# Top_Level.net
KiCad netlist of a schematic drawn in Altium Designer
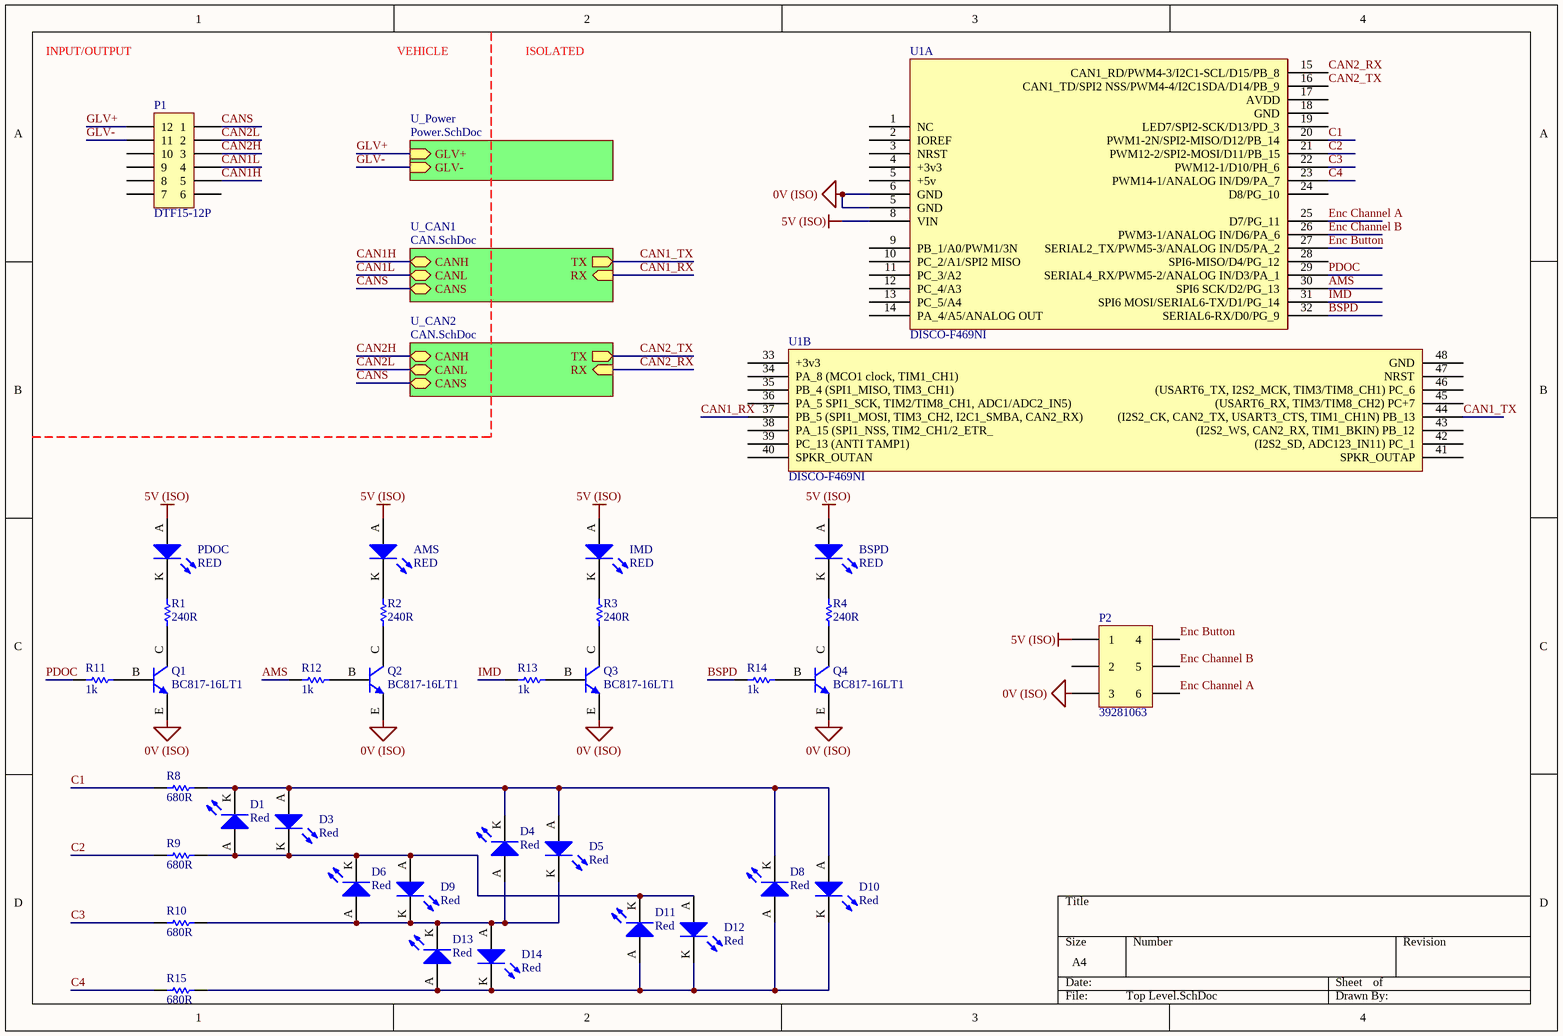
[diagram p0: Top Level.SchDoc]

(export (version "E")
  (design (tool "Eeschema 10.0.6"))
  (components
    (comp (ref "AMS")
      (value "RED")
      (footprint "5MM LED")
      (description "LED RED CLEAR 5MM ROUND T/H")
      (fields (field (name "PART NUMBER") "C503B-GAN-CB0F0791") (field (name "MANUFACTURER") "Cree Inc."))
      (libsource (lib "ts_19-standard-library") (part "LED"))
    )
    (comp (ref "BSPD")
      (value "RED")
      (footprint "5MM LED")
      (description "LED RED CLEAR 5MM ROUND T/H")
      (fields (field (name "PART NUMBER") "C503B-GAN-CB0F0791") (field (name "MANUFACTURER") "Cree Inc."))
      (libsource (lib "ts_19-standard-library") (part "LED"))
    )
    (comp (ref "D1")
      (value "Red")
      (footprint "0805 LED")
      (description "Red LED Indication - Discrete 1.75V 0805 (2012 Metric)")
      (fields (field (name "MANUFACTURER") "ROHM Semiconductor") (field (name "PART NUMBER") "SML-210LTT86"))
      (libsource (lib "ts_19-standard-library") (part "LED"))
    )
    (comp (ref "D3")
      (value "Red")
      (footprint "0805 LED")
      (description "Red LED Indication - Discrete 1.75V 0805 (2012 Metric)")
      (fields (field (name "MANUFACTURER") "ROHM Semiconductor") (field (name "PART NUMBER") "SML-210LTT86"))
      (libsource (lib "ts_19-standard-library") (part "LED"))
    )
    (comp (ref "D4")
      (value "Red")
      (footprint "0805 LED")
      (description "Red LED Indication - Discrete 1.75V 0805 (2012 Metric)")
      (fields (field (name "MANUFACTURER") "ROHM Semiconductor") (field (name "PART NUMBER") "SML-210LTT86"))
      (libsource (lib "ts_19-standard-library") (part "LED"))
    )
    (comp (ref "D5")
      (value "Red")
      (footprint "0805 LED")
      (description "Red LED Indication - Discrete 1.75V 0805 (2012 Metric)")
      (fields (field (name "MANUFACTURER") "ROHM Semiconductor") (field (name "PART NUMBER") "SML-210LTT86"))
      (libsource (lib "ts_19-standard-library") (part "LED"))
    )
    (comp (ref "D6")
      (value "Red")
      (footprint "0805 LED")
      (description "Red LED Indication - Discrete 1.75V 0805 (2012 Metric)")
      (fields (field (name "MANUFACTURER") "ROHM Semiconductor") (field (name "PART NUMBER") "SML-210LTT86"))
      (libsource (lib "ts_19-standard-library") (part "LED"))
    )
    (comp (ref "D8")
      (value "Red")
      (footprint "0805 LED")
      (description "Red LED Indication - Discrete 1.75V 0805 (2012 Metric)")
      (fields (field (name "MANUFACTURER") "ROHM Semiconductor") (field (name "PART NUMBER") "SML-210LTT86"))
      (libsource (lib "ts_19-standard-library") (part "LED"))
    )
    (comp (ref "D9")
      (value "Red")
      (footprint "0805 LED")
      (description "Red LED Indication - Discrete 1.75V 0805 (2012 Metric)")
      (fields (field (name "MANUFACTURER") "ROHM Semiconductor") (field (name "PART NUMBER") "SML-210LTT86"))
      (libsource (lib "ts_19-standard-library") (part "LED"))
    )
    (comp (ref "D10")
      (value "Red")
      (footprint "0805 LED")
      (description "Red LED Indication - Discrete 1.75V 0805 (2012 Metric)")
      (fields (field (name "MANUFACTURER") "ROHM Semiconductor") (field (name "PART NUMBER") "SML-210LTT86"))
      (libsource (lib "ts_19-standard-library") (part "LED"))
    )
    (comp (ref "D11")
      (value "Red")
      (footprint "0805 LED")
      (description "Red LED Indication - Discrete 1.75V 0805 (2012 Metric)")
      (fields (field (name "MANUFACTURER") "ROHM Semiconductor") (field (name "PART NUMBER") "SML-210LTT86"))
      (libsource (lib "ts_19-standard-library") (part "LED"))
    )
    (comp (ref "D12")
      (value "Red")
      (footprint "0805 LED")
      (description "Red LED Indication - Discrete 1.75V 0805 (2012 Metric)")
      (fields (field (name "MANUFACTURER") "ROHM Semiconductor") (field (name "PART NUMBER") "SML-210LTT86"))
      (libsource (lib "ts_19-standard-library") (part "LED"))
    )
    (comp (ref "D13")
      (value "Red")
      (footprint "0805 LED")
      (description "Red LED Indication - Discrete 1.75V 0805 (2012 Metric)")
      (fields (field (name "MANUFACTURER") "ROHM Semiconductor") (field (name "PART NUMBER") "SML-210LTT86"))
      (libsource (lib "ts_19-standard-library") (part "LED"))
    )
    (comp (ref "D14")
      (value "Red")
      (footprint "0805 LED")
      (description "Red LED Indication - Discrete 1.75V 0805 (2012 Metric)")
      (fields (field (name "MANUFACTURER") "ROHM Semiconductor") (field (name "PART NUMBER") "SML-210LTT86"))
      (libsource (lib "ts_19-standard-library") (part "LED"))
    )
    (comp (ref "IMD")
      (value "RED")
      (footprint "5MM LED")
      (description "LED RED CLEAR 5MM ROUND T/H")
      (fields (field (name "PART NUMBER") "C503B-GAN-CB0F0791") (field (name "MANUFACTURER") "Cree Inc."))
      (libsource (lib "ts_19-standard-library") (part "LED"))
    )
    (comp (ref "P1")
      (value "DTF15-12P")
      (footprint "DTF15-12P")
      (fields (field (name "DIGIKEY PART NUMBER") "1734-1647-ND") (field (name "CONTACT") "Copper Alloy"))
      (libsource (lib "ts_20-standard-connectors") (part "DT15-12P"))
    )
    (comp (ref "P2")
      (value "39281063")
      (footprint "39281063")
      (description "Mini-Fit VERT 3x2")
      (fields (field (name "DIGIKEY PART NUMBER") "WM3802-ND") (field (name "CONTACT") "Gold"))
      (libsource (lib "ts_19-standard-connectors") (part "39281063"))
    )
    (comp (ref "PDOC")
      (value "RED")
      (footprint "5MM LED")
      (description "LED RED CLEAR 5MM ROUND T/H")
      (fields (field (name "PART NUMBER") "C503B-GAN-CB0F0791") (field (name "MANUFACTURER") "Cree Inc."))
      (libsource (lib "ts_19-standard-library") (part "LED"))
    )
    (comp (ref "Q1")
      (value "BC817-16LT1")
      (footprint "ON SOT-23 BJT")
      (description "300mW  BJT NPN Transistor")
      (fields
        (field (name "MANUFACTURER") "ON Semiconductor")
        (field (name "DIGIKEY PART NUMBER") "BC817-16LT1OSTR-ND")
      )
      (libsource (lib "ts_19-standard-library") (part "NPN"))
    )
    (comp (ref "Q2")
      (value "BC817-16LT1")
      (footprint "ON SOT-23 BJT")
      (description "300mW  BJT NPN Transistor")
      (fields
        (field (name "MANUFACTURER") "ON Semiconductor")
        (field (name "DIGIKEY PART NUMBER") "BC817-16LT1OSTR-ND")
      )
      (libsource (lib "ts_19-standard-library") (part "NPN"))
    )
    (comp (ref "Q3")
      (value "BC817-16LT1")
      (footprint "ON SOT-23 BJT")
      (description "300mW  BJT NPN Transistor")
      (fields
        (field (name "MANUFACTURER") "ON Semiconductor")
        (field (name "DIGIKEY PART NUMBER") "BC817-16LT1OSTR-ND")
      )
      (libsource (lib "ts_19-standard-library") (part "NPN"))
    )
    (comp (ref "Q4")
      (value "BC817-16LT1")
      (footprint "ON SOT-23 BJT")
      (description "300mW  BJT NPN Transistor")
      (fields
        (field (name "MANUFACTURER") "ON Semiconductor")
        (field (name "DIGIKEY PART NUMBER") "BC817-16LT1OSTR-ND")
      )
      (libsource (lib "ts_19-standard-library") (part "NPN"))
    )
    (comp (ref "R1")
      (value "240R")
      (footprint "0805")
      (fields
        (field (name "PART NUMBER") "RC0805FR07240RL")
        (field (name "MANUFACTURER") "YAGEO")
        (field (name "TOLERANCE") "0.01")
      )
      (libsource (lib "ts_19-standard-library") (part "Resistor"))
    )
    (comp (ref "R2")
      (value "240R")
      (footprint "0805")
      (fields
        (field (name "PART NUMBER") "RC0805FR07240RL")
        (field (name "MANUFACTURER") "YAGEO")
        (field (name "TOLERANCE") "0.01")
      )
      (libsource (lib "ts_19-standard-library") (part "Resistor"))
    )
    (comp (ref "R3")
      (value "240R")
      (footprint "0805")
      (fields
        (field (name "PART NUMBER") "RC0805FR07240RL")
        (field (name "MANUFACTURER") "YAGEO")
        (field (name "TOLERANCE") "0.01")
      )
      (libsource (lib "ts_19-standard-library") (part "Resistor"))
    )
    (comp (ref "R4")
      (value "240R")
      (footprint "0805")
      (fields
        (field (name "PART NUMBER") "RC0805FR07240RL")
        (field (name "MANUFACTURER") "YAGEO")
        (field (name "TOLERANCE") "0.01")
      )
      (libsource (lib "ts_19-standard-library") (part "Resistor"))
    )
    (comp (ref "R8")
      (value "680R")
      (footprint "0805")
      (fields
        (field (name "MANUFACTURER") "YAGEO")
        (field (name "PART NUMBER") "RC0805FR07680RL")
        (field (name "TOLERANCE") "0.01")
      )
      (libsource (lib "ts_19-standard-library") (part "Resistor"))
    )
    (comp (ref "R9")
      (value "680R")
      (footprint "0805")
      (fields
        (field (name "MANUFACTURER") "YAGEO")
        (field (name "PART NUMBER") "RC0805FR07680RL")
        (field (name "TOLERANCE") "0.01")
      )
      (libsource (lib "ts_19-standard-library") (part "Resistor"))
    )
    (comp (ref "R10")
      (value "680R")
      (footprint "0805")
      (fields
        (field (name "MANUFACTURER") "YAGEO")
        (field (name "PART NUMBER") "RC0805FR07680RL")
        (field (name "TOLERANCE") "0.01")
      )
      (libsource (lib "ts_19-standard-library") (part "Resistor"))
    )
    (comp (ref "R11")
      (value "1k")
      (footprint "0805")
      (fields
        (field (name "PART NUMBER") "RC0805FR071KL")
        (field (name "MANUFACTURER") "YAGEO")
        (field (name "TOLERANCE") "0.01")
      )
      (libsource (lib "ts_19-standard-library") (part "Resistor"))
    )
    (comp (ref "R12")
      (value "1k")
      (footprint "0805")
      (fields
        (field (name "PART NUMBER") "RC0805FR071KL")
        (field (name "MANUFACTURER") "YAGEO")
        (field (name "TOLERANCE") "0.01")
      )
      (libsource (lib "ts_19-standard-library") (part "Resistor"))
    )
    (comp (ref "R13")
      (value "1k")
      (footprint "0805")
      (fields
        (field (name "PART NUMBER") "RC0805FR071KL")
        (field (name "MANUFACTURER") "YAGEO")
        (field (name "TOLERANCE") "0.01")
      )
      (libsource (lib "ts_19-standard-library") (part "Resistor"))
    )
    (comp (ref "R14")
      (value "1k")
      (footprint "0805")
      (fields
        (field (name "PART NUMBER") "RC0805FR071KL")
        (field (name "MANUFACTURER") "YAGEO")
        (field (name "TOLERANCE") "0.01")
      )
      (libsource (lib "ts_19-standard-library") (part "Resistor"))
    )
    (comp (ref "R15")
      (value "680R")
      (footprint "0805")
      (fields
        (field (name "MANUFACTURER") "YAGEO")
        (field (name "PART NUMBER") "RC0805FR07680RL")
        (field (name "TOLERANCE") "0.01")
      )
      (libsource (lib "ts_19-standard-library") (part "Resistor"))
    )
    (comp (ref "U1")
      (value "DISCO-F469NI")
      (footprint "DISCO-F469NI")
      (fields
        (field (name "MANUFACTURER") "STMicroelectronics")
        (field (name "DIGIKEY PART NUMBER") "497-15990-ND")
      )
      (libsource (lib "ts_19-standard-library") (part "DISCO-F469NI"))
    )
  )
  (nets
    (net (code "1") (name "/AMS") (class "Default")
      (node (ref "R12") (pin "1") (pinfunction "1_1") (pintype "passive"))
      (node (ref "U1") (pin "30") (pinfunction "SPI6_SCK/D2/PG_13_30") (pintype "passive"))
    )
    (net (code "2") (name "/BSPD") (class "Default")
      (node (ref "R14") (pin "1") (pinfunction "1_1") (pintype "passive"))
      (node (ref "U1") (pin "32") (pinfunction "SERIAL6-RX/D0/PG_9_32") (pintype "passive"))
    )
    (net (code "3") (name "/C1") (class "Default")
      (node (ref "R8") (pin "2") (pinfunction "2_2") (pintype "passive"))
      (node (ref "U1") (pin "20") (pinfunction "PWM1-2N/SPI2-MISO/D12/PB_14_20") (pintype "passive"))
    )
    (net (code "4") (name "/C2") (class "Default")
      (node (ref "R9") (pin "2") (pinfunction "2_2") (pintype "passive"))
      (node (ref "U1") (pin "21") (pinfunction "PWM12-2/SPI2-MOSI/D11/PB_15_21") (pintype "passive"))
    )
    (net (code "5") (name "/C3") (class "Default")
      (node (ref "R10") (pin "2") (pinfunction "2_2") (pintype "passive"))
      (node (ref "U1") (pin "22") (pinfunction "PWM12-1/D10/PH_6_22") (pintype "passive"))
    )
    (net (code "6") (name "/C4") (class "Default")
      (node (ref "R15") (pin "2") (pinfunction "2_2") (pintype "passive"))
      (node (ref "U1") (pin "23") (pinfunction "PWM14-1/ANALOG_IN/D9/PA_7_23") (pintype "passive"))
    )
    (net (code "7") (name "/CAN1H") (class "Default")
      (node (ref "P1") (pin "5") (pinfunction "5_5") (pintype "power_in"))
    )
    (net (code "8") (name "/CAN1L") (class "Default")
      (node (ref "P1") (pin "4") (pinfunction "4_4") (pintype "power_in"))
    )
    (net (code "9") (name "/CAN1_RX") (class "Default")
      (node (ref "U1") (pin "37") (pinfunction "PB_5_(SPI1_MOSI,_TIM3_CH2,_I2C1_SMBA,_CAN2_RX)_37") (pintype "passive"))
    )
    (net (code "10") (name "/CAN1_TX") (class "Default")
      (node (ref "U1") (pin "44") (pinfunction "(I2S2_CK,_CAN2_TX,_USART3_CTS,_TIM1_CH1N)_PB_13_44") (pintype "passive"))
    )
    (net (code "11") (name "/CAN2H") (class "Default")
      (node (ref "P1") (pin "3") (pinfunction "3_3") (pintype "power_in"))
    )
    (net (code "12") (name "/CAN2L") (class "Default")
      (node (ref "P1") (pin "2") (pinfunction "2_2") (pintype "power_in"))
    )
    (net (code "13") (name "/CAN2_RX") (class "Default")
      (node (ref "U1") (pin "15") (pinfunction "CAN1_RD/PWM4-3/I2C1-SCL/D15/PB_8_15") (pintype "passive"))
    )
    (net (code "14") (name "/CAN2_TX") (class "Default")
      (node (ref "U1") (pin "16") (pinfunction "CAN1_TD/SPI2_NSS/PWM4-4/I2C1SDA/D14/PB_9_16") (pintype "passive"))
    )
    (net (code "15") (name "/CANS") (class "Default")
      (node (ref "P1") (pin "1") (pinfunction "1_1") (pintype "power_in"))
    )
    (net (code "16") (name "/Enc Button") (class "Default")
      (node (ref "P2") (pin "4") (pinfunction "4_4") (pintype "passive"))
      (node (ref "U1") (pin "27") (pinfunction "SERIAL2_TX/PWM5-3/ANALOG_IN/D5/PA_2_27") (pintype "passive"))
    )
    (net (code "17") (name "/Enc Channel A") (class "Default")
      (node (ref "P2") (pin "6") (pinfunction "6_6") (pintype "passive"))
      (node (ref "U1") (pin "25") (pinfunction "D7/PG_11_25") (pintype "passive"))
    )
    (net (code "18") (name "/Enc Channel B") (class "Default")
      (node (ref "P2") (pin "5") (pinfunction "5_5") (pintype "passive"))
      (node (ref "U1") (pin "26") (pinfunction "PWM3-1/ANALOG_IN/D6/PA_6_26") (pintype "passive"))
    )
    (net (code "19") (name "/GLV+") (class "Default")
      (node (ref "P1") (pin "12") (pinfunction "12_12") (pintype "passive"))
    )
    (net (code "20") (name "/GLV-") (class "Default")
      (node (ref "P1") (pin "11") (pinfunction "11_11") (pintype "passive"))
    )
    (net (code "21") (name "/IMD") (class "Default")
      (node (ref "R13") (pin "1") (pinfunction "1_1") (pintype "passive"))
      (node (ref "U1") (pin "31") (pinfunction "SPI6_MOSI/SERIAL6-TX/D1/PG_14_31") (pintype "passive"))
    )
    (net (code "22") (name "/PDOC") (class "Default")
      (node (ref "R11") (pin "1") (pinfunction "1_1") (pintype "passive"))
      (node (ref "U1") (pin "29") (pinfunction "SERIAL4_RX/PWM5-2/ANALOG_IN/D3/PA_1_29") (pintype "passive"))
    )
    (net (code "23") (name "0V (ISO)") (class "Default")
      (node (ref "P2") (pin "3") (pinfunction "3_3") (pintype "passive"))
      (node (ref "Q1") (pin "E") (pinfunction "E_E") (pintype "passive"))
      (node (ref "Q2") (pin "E") (pinfunction "E_E") (pintype "passive"))
      (node (ref "Q3") (pin "E") (pinfunction "E_E") (pintype "passive"))
      (node (ref "Q4") (pin "E") (pinfunction "E_E") (pintype "passive"))
      (node (ref "U1") (pin "5") (pinfunction "GND_5") (pintype "passive"))
      (node (ref "U1") (pin "6") (pinfunction "GND_6") (pintype "passive"))
    )
    (net (code "24") (name "5V (ISO)") (class "Default")
      (node (ref "AMS") (pin "A") (pinfunction "A_A") (pintype "passive"))
      (node (ref "BSPD") (pin "A") (pinfunction "A_A") (pintype "passive"))
      (node (ref "IMD") (pin "A") (pinfunction "A_A") (pintype "passive"))
      (node (ref "P2") (pin "1") (pinfunction "1_1") (pintype "passive"))
      (node (ref "PDOC") (pin "A") (pinfunction "A_A") (pintype "passive"))
      (node (ref "U1") (pin "8") (pinfunction "VIN_8") (pintype "passive"))
    )
    (net (code "25") (name "Net-(AMS-PadK)") (class "Default")
      (node (ref "AMS") (pin "K") (pinfunction "K_K") (pintype "passive"))
      (node (ref "R2") (pin "2") (pinfunction "2_2") (pintype "passive"))
    )
    (net (code "26") (name "Net-(BSPD-PadK)") (class "Default")
      (node (ref "BSPD") (pin "K") (pinfunction "K_K") (pintype "passive"))
      (node (ref "R4") (pin "2") (pinfunction "2_2") (pintype "passive"))
    )
    (net (code "27") (name "Net-(D1-PadA)") (class "Default")
      (node (ref "D1") (pin "A") (pinfunction "A_A") (pintype "passive"))
      (node (ref "D11") (pin "K") (pinfunction "K_K") (pintype "passive"))
      (node (ref "D12") (pin "A") (pinfunction "A_A") (pintype "passive"))
      (node (ref "D3") (pin "K") (pinfunction "K_K") (pintype "passive"))
      (node (ref "D6") (pin "K") (pinfunction "K_K") (pintype "passive"))
      (node (ref "D9") (pin "A") (pinfunction "A_A") (pintype "passive"))
      (node (ref "R9") (pin "1") (pinfunction "1_1") (pintype "passive"))
    )
    (net (code "28") (name "Net-(D1-PadK)") (class "Default")
      (node (ref "D1") (pin "K") (pinfunction "K_K") (pintype "passive"))
      (node (ref "D10") (pin "A") (pinfunction "A_A") (pintype "passive"))
      (node (ref "D3") (pin "A") (pinfunction "A_A") (pintype "passive"))
      (node (ref "D4") (pin "K") (pinfunction "K_K") (pintype "passive"))
      (node (ref "D5") (pin "A") (pinfunction "A_A") (pintype "passive"))
      (node (ref "D8") (pin "K") (pinfunction "K_K") (pintype "passive"))
      (node (ref "R8") (pin "1") (pinfunction "1_1") (pintype "passive"))
    )
    (net (code "29") (name "Net-(D10-PadK)") (class "Default")
      (node (ref "D10") (pin "K") (pinfunction "K_K") (pintype "passive"))
      (node (ref "D11") (pin "A") (pinfunction "A_A") (pintype "passive"))
      (node (ref "D12") (pin "K") (pinfunction "K_K") (pintype "passive"))
      (node (ref "D13") (pin "A") (pinfunction "A_A") (pintype "passive"))
      (node (ref "D14") (pin "K") (pinfunction "K_K") (pintype "passive"))
      (node (ref "D8") (pin "A") (pinfunction "A_A") (pintype "passive"))
      (node (ref "R15") (pin "1") (pinfunction "1_1") (pintype "passive"))
    )
    (net (code "30") (name "Net-(D13-PadK)") (class "Default")
      (node (ref "D13") (pin "K") (pinfunction "K_K") (pintype "passive"))
      (node (ref "D14") (pin "A") (pinfunction "A_A") (pintype "passive"))
      (node (ref "D4") (pin "A") (pinfunction "A_A") (pintype "passive"))
      (node (ref "D5") (pin "K") (pinfunction "K_K") (pintype "passive"))
      (node (ref "D6") (pin "A") (pinfunction "A_A") (pintype "passive"))
      (node (ref "D9") (pin "K") (pinfunction "K_K") (pintype "passive"))
      (node (ref "R10") (pin "1") (pinfunction "1_1") (pintype "passive"))
    )
    (net (code "31") (name "Net-(IMD-PadK)") (class "Default")
      (node (ref "IMD") (pin "K") (pinfunction "K_K") (pintype "passive"))
      (node (ref "R3") (pin "2") (pinfunction "2_2") (pintype "passive"))
    )
    (net (code "32") (name "Net-(PDOC-PadK)") (class "Default")
      (node (ref "PDOC") (pin "K") (pinfunction "K_K") (pintype "passive"))
      (node (ref "R1") (pin "2") (pinfunction "2_2") (pintype "passive"))
    )
    (net (code "33") (name "Net-(Q1-PadB)") (class "Default")
      (node (ref "Q1") (pin "B") (pinfunction "B_B") (pintype "passive"))
      (node (ref "R11") (pin "2") (pinfunction "2_2") (pintype "passive"))
    )
    (net (code "34") (name "Net-(Q1-PadC)") (class "Default")
      (node (ref "Q1") (pin "C") (pinfunction "C_C") (pintype "passive"))
      (node (ref "R1") (pin "1") (pinfunction "1_1") (pintype "passive"))
    )
    (net (code "35") (name "Net-(Q2-PadB)") (class "Default")
      (node (ref "Q2") (pin "B") (pinfunction "B_B") (pintype "passive"))
      (node (ref "R12") (pin "2") (pinfunction "2_2") (pintype "passive"))
    )
    (net (code "36") (name "Net-(Q2-PadC)") (class "Default")
      (node (ref "Q2") (pin "C") (pinfunction "C_C") (pintype "passive"))
      (node (ref "R2") (pin "1") (pinfunction "1_1") (pintype "passive"))
    )
    (net (code "37") (name "Net-(Q3-PadB)") (class "Default")
      (node (ref "Q3") (pin "B") (pinfunction "B_B") (pintype "passive"))
      (node (ref "R13") (pin "2") (pinfunction "2_2") (pintype "passive"))
    )
    (net (code "38") (name "Net-(Q3-PadC)") (class "Default")
      (node (ref "Q3") (pin "C") (pinfunction "C_C") (pintype "passive"))
      (node (ref "R3") (pin "1") (pinfunction "1_1") (pintype "passive"))
    )
    (net (code "39") (name "Net-(Q4-PadB)") (class "Default")
      (node (ref "Q4") (pin "B") (pinfunction "B_B") (pintype "passive"))
      (node (ref "R14") (pin "2") (pinfunction "2_2") (pintype "passive"))
    )
    (net (code "40") (name "Net-(Q4-PadC)") (class "Default")
      (node (ref "Q4") (pin "C") (pinfunction "C_C") (pintype "passive"))
      (node (ref "R4") (pin "1") (pinfunction "1_1") (pintype "passive"))
    )
    (net (code "41") (name "unconnected-(P1-Pad6)") (class "Default")
      (node (ref "P1") (pin "6") (pinfunction "6_6") (pintype "power_in"))
    )
    (net (code "42") (name "unconnected-(P1-Pad7)") (class "Default")
      (node (ref "P1") (pin "7") (pinfunction "7_7") (pintype "passive"))
    )
    (net (code "43") (name "unconnected-(P1-Pad8)") (class "Default")
      (node (ref "P1") (pin "8") (pinfunction "8_8") (pintype "passive"))
    )
    (net (code "44") (name "unconnected-(P1-Pad9)") (class "Default")
      (node (ref "P1") (pin "9") (pinfunction "9_9") (pintype "passive"))
    )
    (net (code "45") (name "unconnected-(P1-Pad10)") (class "Default")
      (node (ref "P1") (pin "10") (pinfunction "10_10") (pintype "passive"))
    )
    (net (code "46") (name "unconnected-(P2-Pad2)") (class "Default")
      (node (ref "P2") (pin "2") (pinfunction "2_2") (pintype "passive"))
    )
    (net (code "47") (name "unconnected-(U1A-+3v3-Pad4)") (class "Default")
      (node (ref "U1") (pin "4") (pinfunction "+3v3_4") (pintype "passive"))
    )
    (net (code "48") (name "unconnected-(U1A-+5v-Pad5)") (class "Default")
      (node (ref "U1") (pin "5") (pinfunction "+5v_5") (pintype "passive"))
    )
    (net (code "49") (name "unconnected-(U1A-AVDD-Pad17)") (class "Default")
      (node (ref "U1") (pin "17") (pinfunction "AVDD_17") (pintype "passive"))
    )
    (net (code "50") (name "unconnected-(U1A-D8{slash}PG_10-Pad24)") (class "Default")
      (node (ref "U1") (pin "24") (pinfunction "D8/PG_10_24") (pintype "passive"))
    )
    (net (code "51") (name "unconnected-(U1A-GND-Pad18)") (class "Default")
      (node (ref "U1") (pin "18") (pinfunction "GND_18") (pintype "passive"))
    )
    (net (code "52") (name "unconnected-(U1A-IOREF-Pad2)") (class "Default")
      (node (ref "U1") (pin "2") (pinfunction "IOREF_2") (pintype "passive"))
    )
    (net (code "53") (name "unconnected-(U1A-LED7{slash}SPI2-SCK{slash}D13{slash}PD_3-Pad19)") (class "Default")
      (node (ref "U1") (pin "19") (pinfunction "LED7/SPI2-SCK/D13/PD_3_19") (pintype "passive"))
    )
    (net (code "54") (name "unconnected-(U1A-NC-Pad1)") (class "Default")
      (node (ref "U1") (pin "1") (pinfunction "NC_1") (pintype "passive"))
    )
    (net (code "55") (name "unconnected-(U1A-NRST-Pad3)") (class "Default")
      (node (ref "U1") (pin "3") (pinfunction "NRST_3") (pintype "passive"))
    )
    (net (code "56") (name "unconnected-(U1A-PA_4{slash}A5{slash}ANALOG_OUT-Pad14)") (class "Default")
      (node (ref "U1") (pin "14") (pinfunction "PA_4/A5/ANALOG_OUT_14") (pintype "passive"))
    )
    (net (code "57") (name "unconnected-(U1A-PB_1{slash}A0{slash}PWM1{slash}3N-Pad9)") (class "Default")
      (node (ref "U1") (pin "9") (pinfunction "PB_1/A0/PWM1/3N_9") (pintype "passive"))
    )
    (net (code "58") (name "unconnected-(U1A-PC_2{slash}A1{slash}SPI2_MISO-Pad10)") (class "Default")
      (node (ref "U1") (pin "10") (pinfunction "PC_2/A1/SPI2_MISO_10") (pintype "passive"))
    )
    (net (code "59") (name "unconnected-(U1A-PC_3{slash}A2-Pad11)") (class "Default")
      (node (ref "U1") (pin "11") (pinfunction "PC_3/A2_11") (pintype "passive"))
    )
    (net (code "60") (name "unconnected-(U1A-PC_4{slash}A3-Pad12)") (class "Default")
      (node (ref "U1") (pin "12") (pinfunction "PC_4/A3_12") (pintype "passive"))
    )
    (net (code "61") (name "unconnected-(U1A-PC_5{slash}A4-Pad13)") (class "Default")
      (node (ref "U1") (pin "13") (pinfunction "PC_5/A4_13") (pintype "passive"))
    )
    (net (code "62") (name "unconnected-(U1A-SPI6-MISO{slash}D4{slash}PG_12-Pad28)") (class "Default")
      (node (ref "U1") (pin "28") (pinfunction "SPI6-MISO/D4/PG_12_28") (pintype "passive"))
    )
    (net (code "63") (name "unconnected-(U1B-(I2S2_SD,_ADC123_IN11)_PC_1-Pad42)") (class "Default")
      (node (ref "U1") (pin "42") (pinfunction "(I2S2_SD,_ADC123_IN11)_PC_1_42") (pintype "passive"))
    )
    (net (code "64") (name "unconnected-(U1B-(I2S2_WS,_CAN2_RX,_TIM1_BKIN)_PB_12-Pad43)") (class "Default")
      (node (ref "U1") (pin "43") (pinfunction "(I2S2_WS,_CAN2_RX,_TIM1_BKIN)_PB_12_43") (pintype "passive"))
    )
    (net (code "65") (name "unconnected-(U1B-(USART6_RX,_TIM3{slash}TIM8_CH2)_PC+7-Pad45)") (class "Default")
      (node (ref "U1") (pin "45") (pinfunction "(USART6_RX,_TIM3/TIM8_CH2)_PC+7_45") (pintype "passive"))
    )
    (net (code "66") (name "unconnected-(U1B-(USART6_TX,_I2S2_MCK,_TIM3{slash}TIM8_CH1)_PC_6-Pad46)") (class "Default")
      (node (ref "U1") (pin "46") (pinfunction "(USART6_TX,_I2S2_MCK,_TIM3/TIM8_CH1)_PC_6_46") (pintype "passive"))
    )
    (net (code "67") (name "unconnected-(U1B-+3v3-Pad33)") (class "Default")
      (node (ref "U1") (pin "33") (pinfunction "+3v3_33") (pintype "passive"))
    )
    (net (code "68") (name "unconnected-(U1B-GND-Pad48)") (class "Default")
      (node (ref "U1") (pin "48") (pinfunction "GND_48") (pintype "passive"))
    )
    (net (code "69") (name "unconnected-(U1B-NRST-Pad47)") (class "Default")
      (node (ref "U1") (pin "47") (pinfunction "NRST_47") (pintype "passive"))
    )
    (net (code "70") (name "unconnected-(U1B-PA_5_SPI1_SCK,_TIM2{slash}TIM8_CH1,_ADC1{slash}ADC2_IN5)-Pad36)") (class "Default")
      (node (ref "U1") (pin "36") (pinfunction "PA_5_SPI1_SCK,_TIM2/TIM8_CH1,_ADC1/ADC2_IN5)_36") (pintype "passive"))
    )
    (net (code "71") (name "unconnected-(U1B-PA_8_(MCO1_clock,_TIM1_CH1)-Pad34)") (class "Default")
      (node (ref "U1") (pin "34") (pinfunction "PA_8_(MCO1_clock,_TIM1_CH1)_34") (pintype "passive"))
    )
    (net (code "72") (name "unconnected-(U1B-PA_15_(SPI1_NSS,_TIM2_CH1{slash}2_ETR_-Pad38)") (class "Default")
      (node (ref "U1") (pin "38") (pinfunction "PA_15_(SPI1_NSS,_TIM2_CH1/2_ETR__38") (pintype "passive"))
    )
    (net (code "73") (name "unconnected-(U1B-PB_4_(SPI1_MISO,_TIM3_CH1)-Pad35)") (class "Default")
      (node (ref "U1") (pin "35") (pinfunction "PB_4_(SPI1_MISO,_TIM3_CH1)_35") (pintype "passive"))
    )
    (net (code "74") (name "unconnected-(U1B-PC_13_(ANTI_TAMP1)-Pad39)") (class "Default")
      (node (ref "U1") (pin "39") (pinfunction "PC_13_(ANTI_TAMP1)_39") (pintype "passive"))
    )
    (net (code "75") (name "unconnected-(U1B-SPKR_OUTAN-Pad40)") (class "Default")
      (node (ref "U1") (pin "40") (pinfunction "SPKR_OUTAN_40") (pintype "passive"))
    )
    (net (code "76") (name "unconnected-(U1B-SPKR_OUTAP-Pad41)") (class "Default")
      (node (ref "U1") (pin "41") (pinfunction "SPKR_OUTAP_41") (pintype "passive"))
    )
  )
)
